# Connectors.net
KiCad netlist of a schematic drawn in Altium Designer
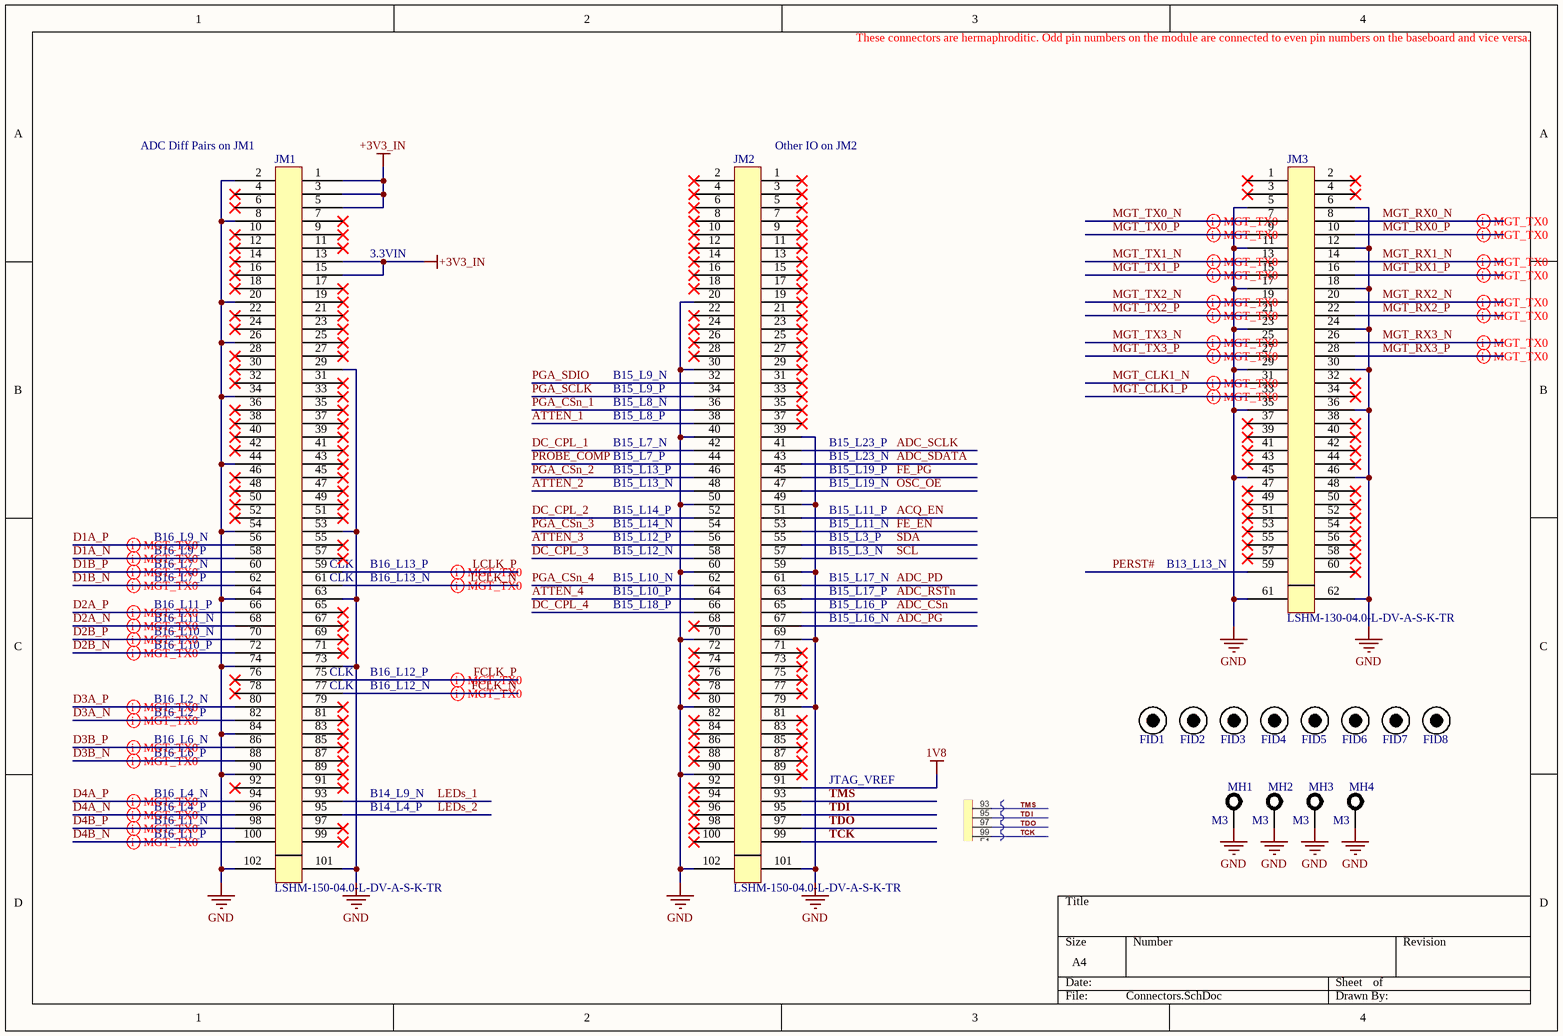
[diagram p0: Connectors.SchDoc]

(export (version "E")
  (design (tool "Eeschema 10.0.6"))
  (components
    (comp (ref "FID1") (value "PCB") (footprint "GEN_FID") (libsource (lib "DSO") (part "FID 1mm")))
    (comp (ref "FID2") (value "PCB") (footprint "GEN_FID") (libsource (lib "DSO") (part "FID 1mm")))
    (comp (ref "FID3") (value "PCB") (footprint "GEN_FID") (libsource (lib "DSO") (part "FID 1mm")))
    (comp (ref "FID4") (value "PCB") (footprint "GEN_FID") (libsource (lib "DSO") (part "FID 1mm")))
    (comp (ref "FID5") (value "PCB") (footprint "GEN_FID") (libsource (lib "DSO") (part "FID 1mm")))
    (comp (ref "FID6") (value "PCB") (footprint "GEN_FID") (libsource (lib "DSO") (part "FID 1mm")))
    (comp (ref "FID7") (value "PCB") (footprint "GEN_FID") (libsource (lib "DSO") (part "FID 1mm")))
    (comp (ref "FID8") (value "PCB") (footprint "GEN_FID") (libsource (lib "DSO") (part "FID 1mm")))
    (comp (ref "JM1")
      (value "LSHM-150-04.0-L-DV-A-S-K-TR")
      (footprint "SAM_LSHM-150-XX.X-XX-DV-A-S")
      (libsource (lib "DSO") (part "CONN LSHM-150-04.0-L-DV-A-S-K-TR"))
    )
    (comp (ref "JM2")
      (value "LSHM-150-04.0-L-DV-A-S-K-TR")
      (footprint "SAM_LSHM-150-XX.X-XX-DV-A-S")
      (libsource (lib "DSO") (part "CONN LSHM-150-04.0-L-DV-A-S-K-TR"))
    )
    (comp (ref "JM3")
      (value "LSHM-130-04.0-L-DV-A-S-K-TR")
      (footprint "SAM_LSHM-130-XX.X-XX-DV-A-S")
      (libsource (lib "DSO") (part "CONN LSHM-130-04.0-L-DV-A-S-K-TR"))
    )
    (comp (ref "MH1") (value "M3") (footprint "MH M3") (libsource (lib "DSO") (part "MH M3")))
    (comp (ref "MH2") (value "M3") (footprint "MH M3") (libsource (lib "DSO") (part "MH M3")))
    (comp (ref "MH3") (value "M3") (footprint "MH M3") (libsource (lib "DSO") (part "MH M3")))
    (comp (ref "MH4") (value "M3") (footprint "MH M3") (libsource (lib "DSO") (part "MH M3")))
  )
  (nets
    (net (code "1") (name "+3V3_IN") (class "Default")
      (node (ref "JM1") (pin "1") (pinfunction "1_1") (pintype "passive"))
      (node (ref "JM1") (pin "13") (pinfunction "13_13") (pintype "passive"))
      (node (ref "JM1") (pin "15") (pinfunction "15_15") (pintype "passive"))
      (node (ref "JM1") (pin "3") (pinfunction "3_3") (pintype "passive"))
      (node (ref "JM1") (pin "5") (pinfunction "5_5") (pintype "passive"))
    )
    (net (code "2") (name "/ACQ_EN") (class "Default")
      (node (ref "JM2") (pin "51") (pinfunction "51_51") (pintype "passive"))
    )
    (net (code "3") (name "/ADC_CSn") (class "Default")
      (node (ref "JM2") (pin "65") (pinfunction "65_65") (pintype "passive"))
    )
    (net (code "4") (name "/ADC_PD") (class "Default")
      (node (ref "JM2") (pin "61") (pinfunction "61_61") (pintype "passive"))
    )
    (net (code "5") (name "/ADC_PG") (class "Default")
      (node (ref "JM2") (pin "67") (pinfunction "67_67") (pintype "passive"))
    )
    (net (code "6") (name "/ADC_RSTn") (class "Default")
      (node (ref "JM2") (pin "63") (pinfunction "63_63") (pintype "passive"))
    )
    (net (code "7") (name "/ADC_SCLK") (class "Default")
      (node (ref "JM2") (pin "41") (pinfunction "41_41") (pintype "passive"))
    )
    (net (code "8") (name "/ADC_SDATA") (class "Default")
      (node (ref "JM2") (pin "43") (pinfunction "43_43") (pintype "passive"))
    )
    (net (code "9") (name "/ATTEN_1") (class "Default")
      (node (ref "JM2") (pin "38") (pinfunction "38_38") (pintype "passive"))
    )
    (net (code "10") (name "/ATTEN_2") (class "Default")
      (node (ref "JM2") (pin "48") (pinfunction "48_48") (pintype "passive"))
    )
    (net (code "11") (name "/ATTEN_3") (class "Default")
      (node (ref "JM2") (pin "56") (pinfunction "56_56") (pintype "passive"))
    )
    (net (code "12") (name "/ATTEN_4") (class "Default")
      (node (ref "JM2") (pin "64") (pinfunction "64_64") (pintype "passive"))
    )
    (net (code "13") (name "/D1A_N") (class "Default")
      (node (ref "JM1") (pin "58") (pinfunction "58_58") (pintype "passive"))
    )
    (net (code "14") (name "/D1A_P") (class "Default")
      (node (ref "JM1") (pin "56") (pinfunction "56_56") (pintype "passive"))
    )
    (net (code "15") (name "/D1B_N") (class "Default")
      (node (ref "JM1") (pin "62") (pinfunction "62_62") (pintype "passive"))
    )
    (net (code "16") (name "/D1B_P") (class "Default")
      (node (ref "JM1") (pin "60") (pinfunction "60_60") (pintype "passive"))
    )
    (net (code "17") (name "/D2A_N") (class "Default")
      (node (ref "JM1") (pin "68") (pinfunction "68_68") (pintype "passive"))
    )
    (net (code "18") (name "/D2A_P") (class "Default")
      (node (ref "JM1") (pin "66") (pinfunction "66_66") (pintype "passive"))
    )
    (net (code "19") (name "/D2B_N") (class "Default")
      (node (ref "JM1") (pin "72") (pinfunction "72_72") (pintype "passive"))
    )
    (net (code "20") (name "/D2B_P") (class "Default")
      (node (ref "JM1") (pin "70") (pinfunction "70_70") (pintype "passive"))
    )
    (net (code "21") (name "/D3A_N") (class "Default")
      (node (ref "JM1") (pin "82") (pinfunction "82_82") (pintype "passive"))
    )
    (net (code "22") (name "/D3A_P") (class "Default")
      (node (ref "JM1") (pin "80") (pinfunction "80_80") (pintype "passive"))
    )
    (net (code "23") (name "/D3B_N") (class "Default")
      (node (ref "JM1") (pin "88") (pinfunction "88_88") (pintype "passive"))
    )
    (net (code "24") (name "/D3B_P") (class "Default")
      (node (ref "JM1") (pin "86") (pinfunction "86_86") (pintype "passive"))
    )
    (net (code "25") (name "/D4A_N") (class "Default")
      (node (ref "JM1") (pin "96") (pinfunction "96_96") (pintype "passive"))
    )
    (net (code "26") (name "/D4A_P") (class "Default")
      (node (ref "JM1") (pin "94") (pinfunction "94_94") (pintype "passive"))
    )
    (net (code "27") (name "/D4B_N") (class "Default")
      (node (ref "JM1") (pin "100") (pinfunction "100_100") (pintype "passive"))
    )
    (net (code "28") (name "/D4B_P") (class "Default")
      (node (ref "JM1") (pin "98") (pinfunction "98_98") (pintype "passive"))
    )
    (net (code "29") (name "/DC_CPL_1") (class "Default")
      (node (ref "JM2") (pin "42") (pinfunction "42_42") (pintype "passive"))
    )
    (net (code "30") (name "/DC_CPL_2") (class "Default")
      (node (ref "JM2") (pin "52") (pinfunction "52_52") (pintype "passive"))
    )
    (net (code "31") (name "/DC_CPL_3") (class "Default")
      (node (ref "JM2") (pin "58") (pinfunction "58_58") (pintype "passive"))
    )
    (net (code "32") (name "/DC_CPL_4") (class "Default")
      (node (ref "JM2") (pin "66") (pinfunction "66_66") (pintype "passive"))
    )
    (net (code "33") (name "/FCLK_N") (class "Default")
      (node (ref "JM1") (pin "77") (pinfunction "77_77") (pintype "passive"))
    )
    (net (code "34") (name "/FCLK_P") (class "Default")
      (node (ref "JM1") (pin "75") (pinfunction "75_75") (pintype "passive"))
    )
    (net (code "35") (name "/FE_EN") (class "Default")
      (node (ref "JM2") (pin "53") (pinfunction "53_53") (pintype "passive"))
    )
    (net (code "36") (name "/FE_PG") (class "Default")
      (node (ref "JM2") (pin "45") (pinfunction "45_45") (pintype "passive"))
    )
    (net (code "37") (name "/LCLK_N") (class "Default")
      (node (ref "JM1") (pin "61") (pinfunction "61_61") (pintype "passive"))
    )
    (net (code "38") (name "/LCLK_P") (class "Default")
      (node (ref "JM1") (pin "59") (pinfunction "59_59") (pintype "passive"))
    )
    (net (code "39") (name "/LEDs_1") (class "Default")
      (node (ref "JM1") (pin "93") (pinfunction "93_93") (pintype "passive"))
    )
    (net (code "40") (name "/LEDs_2") (class "Default")
      (node (ref "JM1") (pin "95") (pinfunction "95_95") (pintype "passive"))
    )
    (net (code "41") (name "/MGT_CLK1_N") (class "Default")
      (node (ref "JM3") (pin "31") (pinfunction "31_31") (pintype "passive"))
    )
    (net (code "42") (name "/MGT_CLK1_P") (class "Default")
      (node (ref "JM3") (pin "33") (pinfunction "33_33") (pintype "passive"))
    )
    (net (code "43") (name "/MGT_RX0_N") (class "Default")
      (node (ref "JM3") (pin "8") (pinfunction "8_8") (pintype "passive"))
    )
    (net (code "44") (name "/MGT_RX0_P") (class "Default")
      (node (ref "JM3") (pin "10") (pinfunction "10_10") (pintype "passive"))
    )
    (net (code "45") (name "/MGT_RX1_N") (class "Default")
      (node (ref "JM3") (pin "14") (pinfunction "14_14") (pintype "passive"))
    )
    (net (code "46") (name "/MGT_RX1_P") (class "Default")
      (node (ref "JM3") (pin "16") (pinfunction "16_16") (pintype "passive"))
    )
    (net (code "47") (name "/MGT_RX2_N") (class "Default")
      (node (ref "JM3") (pin "20") (pinfunction "20_20") (pintype "passive"))
    )
    (net (code "48") (name "/MGT_RX2_P") (class "Default")
      (node (ref "JM3") (pin "22") (pinfunction "22_22") (pintype "passive"))
    )
    (net (code "49") (name "/MGT_RX3_N") (class "Default")
      (node (ref "JM3") (pin "26") (pinfunction "26_26") (pintype "passive"))
    )
    (net (code "50") (name "/MGT_RX3_P") (class "Default")
      (node (ref "JM3") (pin "28") (pinfunction "28_28") (pintype "passive"))
    )
    (net (code "51") (name "/MGT_TX0_N") (class "Default")
      (node (ref "JM3") (pin "7") (pinfunction "7_7") (pintype "passive"))
    )
    (net (code "52") (name "/MGT_TX0_P") (class "Default")
      (node (ref "JM3") (pin "9") (pinfunction "9_9") (pintype "passive"))
    )
    (net (code "53") (name "/MGT_TX1_N") (class "Default")
      (node (ref "JM3") (pin "13") (pinfunction "13_13") (pintype "passive"))
    )
    (net (code "54") (name "/MGT_TX1_P") (class "Default")
      (node (ref "JM3") (pin "15") (pinfunction "15_15") (pintype "passive"))
    )
    (net (code "55") (name "/MGT_TX2_N") (class "Default")
      (node (ref "JM3") (pin "19") (pinfunction "19_19") (pintype "passive"))
    )
    (net (code "56") (name "/MGT_TX2_P") (class "Default")
      (node (ref "JM3") (pin "21") (pinfunction "21_21") (pintype "passive"))
    )
    (net (code "57") (name "/MGT_TX3_N") (class "Default")
      (node (ref "JM3") (pin "25") (pinfunction "25_25") (pintype "passive"))
    )
    (net (code "58") (name "/MGT_TX3_P") (class "Default")
      (node (ref "JM3") (pin "27") (pinfunction "27_27") (pintype "passive"))
    )
    (net (code "59") (name "/OSC_OE") (class "Default")
      (node (ref "JM2") (pin "47") (pinfunction "47_47") (pintype "passive"))
    )
    (net (code "60") (name "/PERST#") (class "Default")
      (node (ref "JM3") (pin "59") (pinfunction "59_59") (pintype "passive"))
    )
    (net (code "61") (name "/PGA_CSn_1") (class "Default")
      (node (ref "JM2") (pin "36") (pinfunction "36_36") (pintype "passive"))
    )
    (net (code "62") (name "/PGA_CSn_2") (class "Default")
      (node (ref "JM2") (pin "46") (pinfunction "46_46") (pintype "passive"))
    )
    (net (code "63") (name "/PGA_CSn_3") (class "Default")
      (node (ref "JM2") (pin "54") (pinfunction "54_54") (pintype "passive"))
    )
    (net (code "64") (name "/PGA_CSn_4") (class "Default")
      (node (ref "JM2") (pin "62") (pinfunction "62_62") (pintype "passive"))
    )
    (net (code "65") (name "/PGA_SCLK") (class "Default")
      (node (ref "JM2") (pin "34") (pinfunction "34_34") (pintype "passive"))
    )
    (net (code "66") (name "/PGA_SDIO") (class "Default")
      (node (ref "JM2") (pin "32") (pinfunction "32_32") (pintype "passive"))
    )
    (net (code "67") (name "/PROBE_COMP") (class "Default")
      (node (ref "JM2") (pin "44") (pinfunction "44_44") (pintype "passive"))
    )
    (net (code "68") (name "/SCL") (class "Default")
      (node (ref "JM2") (pin "57") (pinfunction "57_57") (pintype "passive"))
    )
    (net (code "69") (name "/SDA") (class "Default")
      (node (ref "JM2") (pin "55") (pinfunction "55_55") (pintype "passive"))
    )
    (net (code "70") (name "/TCK") (class "Default")
      (node (ref "JM2") (pin "99") (pinfunction "99_99") (pintype "passive"))
    )
    (net (code "71") (name "/TDI") (class "Default")
      (node (ref "JM2") (pin "95") (pinfunction "95_95") (pintype "passive"))
    )
    (net (code "72") (name "/TDO") (class "Default")
      (node (ref "JM2") (pin "97") (pinfunction "97_97") (pintype "passive"))
    )
    (net (code "73") (name "/TMS") (class "Default")
      (node (ref "JM2") (pin "93") (pinfunction "93_93") (pintype "passive"))
    )
    (net (code "74") (name "1V8") (class "Default")
      (node (ref "JM2") (pin "91") (pinfunction "91_91") (pintype "passive"))
    )
    (net (code "75") (name "GND") (class "Default")
      (node (ref "JM1") (pin "101") (pinfunction "101_101") (pintype "passive"))
      (node (ref "JM1") (pin "102") (pinfunction "102_102") (pintype "passive"))
      (node (ref "JM1") (pin "2") (pinfunction "2_2") (pintype "passive"))
      (node (ref "JM1") (pin "20") (pinfunction "20_20") (pintype "passive"))
      (node (ref "JM1") (pin "26") (pinfunction "26_26") (pintype "passive"))
      (node (ref "JM1") (pin "29") (pinfunction "29_29") (pintype "passive"))
      (node (ref "JM1") (pin "34") (pinfunction "34_34") (pintype "passive"))
      (node (ref "JM1") (pin "44") (pinfunction "44_44") (pintype "passive"))
      (node (ref "JM1") (pin "53") (pinfunction "53_53") (pintype "passive"))
      (node (ref "JM1") (pin "54") (pinfunction "54_54") (pintype "passive"))
      (node (ref "JM1") (pin "63") (pinfunction "63_63") (pintype "passive"))
      (node (ref "JM1") (pin "64") (pinfunction "64_64") (pintype "passive"))
      (node (ref "JM1") (pin "73") (pinfunction "73_73") (pintype "passive"))
      (node (ref "JM1") (pin "74") (pinfunction "74_74") (pintype "passive"))
      (node (ref "JM1") (pin "8") (pinfunction "8_8") (pintype "passive"))
      (node (ref "JM1") (pin "84") (pinfunction "84_84") (pintype "passive"))
      (node (ref "JM1") (pin "90") (pinfunction "90_90") (pintype "passive"))
      (node (ref "JM2") (pin "101") (pinfunction "101_101") (pintype "passive"))
      (node (ref "JM2") (pin "102") (pinfunction "102_102") (pintype "passive"))
      (node (ref "JM2") (pin "20") (pinfunction "20_20") (pintype "passive"))
      (node (ref "JM2") (pin "30") (pinfunction "30_30") (pintype "passive"))
      (node (ref "JM2") (pin "39") (pinfunction "39_39") (pintype "passive"))
      (node (ref "JM2") (pin "40") (pinfunction "40_40") (pintype "passive"))
      (node (ref "JM2") (pin "49") (pinfunction "49_49") (pintype "passive"))
      (node (ref "JM2") (pin "50") (pinfunction "50_50") (pintype "passive"))
      (node (ref "JM2") (pin "59") (pinfunction "59_59") (pintype "passive"))
      (node (ref "JM2") (pin "60") (pinfunction "60_60") (pintype "passive"))
      (node (ref "JM2") (pin "69") (pinfunction "69_69") (pintype "passive"))
      (node (ref "JM2") (pin "70") (pinfunction "70_70") (pintype "passive"))
      (node (ref "JM2") (pin "79") (pinfunction "79_79") (pintype "passive"))
      (node (ref "JM2") (pin "80") (pinfunction "80_80") (pintype "passive"))
      (node (ref "JM2") (pin "90") (pinfunction "90_90") (pintype "passive"))
      (node (ref "JM3") (pin "11") (pinfunction "11_11") (pintype "passive"))
      (node (ref "JM3") (pin "12") (pinfunction "12_12") (pintype "passive"))
      (node (ref "JM3") (pin "17") (pinfunction "17_17") (pintype "passive"))
      (node (ref "JM3") (pin "18") (pinfunction "18_18") (pintype "passive"))
      (node (ref "JM3") (pin "23") (pinfunction "23_23") (pintype "passive"))
      (node (ref "JM3") (pin "24") (pinfunction "24_24") (pintype "passive"))
      (node (ref "JM3") (pin "29") (pinfunction "29_29") (pintype "passive"))
      (node (ref "JM3") (pin "30") (pinfunction "30_30") (pintype "passive"))
      (node (ref "JM3") (pin "35") (pinfunction "35_35") (pintype "passive"))
      (node (ref "JM3") (pin "36") (pinfunction "36_36") (pintype "passive"))
      (node (ref "JM3") (pin "45") (pinfunction "45_45") (pintype "passive"))
      (node (ref "JM3") (pin "46") (pinfunction "46_46") (pintype "passive"))
      (node (ref "JM3") (pin "5") (pinfunction "5_5") (pintype "passive"))
      (node (ref "JM3") (pin "6") (pinfunction "6_6") (pintype "passive"))
      (node (ref "JM3") (pin "61") (pinfunction "61_61") (pintype "passive"))
      (node (ref "JM3") (pin "62") (pinfunction "62_62") (pintype "passive"))
      (node (ref "MH1") (pin "1") (pinfunction "1_1") (pintype "passive"))
      (node (ref "MH2") (pin "1") (pinfunction "1_1") (pintype "passive"))
      (node (ref "MH3") (pin "1") (pinfunction "1_1") (pintype "passive"))
      (node (ref "MH4") (pin "1") (pinfunction "1_1") (pintype "passive"))
    )
    (net (code "76") (name "unconnected-(JM1-Pad4)") (class "Default")
      (node (ref "JM1") (pin "4") (pinfunction "4_4") (pintype "passive+no_connect"))
    )
    (net (code "77") (name "unconnected-(JM1-Pad6)") (class "Default")
      (node (ref "JM1") (pin "6") (pinfunction "6_6") (pintype "passive+no_connect"))
    )
    (net (code "78") (name "unconnected-(JM1-Pad7)") (class "Default")
      (node (ref "JM1") (pin "7") (pinfunction "7_7") (pintype "passive+no_connect"))
    )
    (net (code "79") (name "unconnected-(JM1-Pad9)") (class "Default")
      (node (ref "JM1") (pin "9") (pinfunction "9_9") (pintype "passive+no_connect"))
    )
    (net (code "80") (name "unconnected-(JM1-Pad10)") (class "Default")
      (node (ref "JM1") (pin "10") (pinfunction "10_10") (pintype "passive+no_connect"))
    )
    (net (code "81") (name "unconnected-(JM1-Pad11)") (class "Default")
      (node (ref "JM1") (pin "11") (pinfunction "11_11") (pintype "passive+no_connect"))
    )
    (net (code "82") (name "unconnected-(JM1-Pad12)") (class "Default")
      (node (ref "JM1") (pin "12") (pinfunction "12_12") (pintype "passive+no_connect"))
    )
    (net (code "83") (name "unconnected-(JM1-Pad14)") (class "Default")
      (node (ref "JM1") (pin "14") (pinfunction "14_14") (pintype "passive+no_connect"))
    )
    (net (code "84") (name "unconnected-(JM1-Pad16)") (class "Default")
      (node (ref "JM1") (pin "16") (pinfunction "16_16") (pintype "passive+no_connect"))
    )
    (net (code "85") (name "unconnected-(JM1-Pad17)") (class "Default")
      (node (ref "JM1") (pin "17") (pinfunction "17_17") (pintype "passive+no_connect"))
    )
    (net (code "86") (name "unconnected-(JM1-Pad18)") (class "Default")
      (node (ref "JM1") (pin "18") (pinfunction "18_18") (pintype "passive+no_connect"))
    )
    (net (code "87") (name "unconnected-(JM1-Pad19)") (class "Default")
      (node (ref "JM1") (pin "19") (pinfunction "19_19") (pintype "passive+no_connect"))
    )
    (net (code "88") (name "unconnected-(JM1-Pad21)") (class "Default")
      (node (ref "JM1") (pin "21") (pinfunction "21_21") (pintype "passive+no_connect"))
    )
    (net (code "89") (name "unconnected-(JM1-Pad22)") (class "Default")
      (node (ref "JM1") (pin "22") (pinfunction "22_22") (pintype "passive+no_connect"))
    )
    (net (code "90") (name "unconnected-(JM1-Pad23)") (class "Default")
      (node (ref "JM1") (pin "23") (pinfunction "23_23") (pintype "passive+no_connect"))
    )
    (net (code "91") (name "unconnected-(JM1-Pad24)") (class "Default")
      (node (ref "JM1") (pin "24") (pinfunction "24_24") (pintype "passive+no_connect"))
    )
    (net (code "92") (name "unconnected-(JM1-Pad25)") (class "Default")
      (node (ref "JM1") (pin "25") (pinfunction "25_25") (pintype "passive+no_connect"))
    )
    (net (code "93") (name "unconnected-(JM1-Pad27)") (class "Default")
      (node (ref "JM1") (pin "27") (pinfunction "27_27") (pintype "passive+no_connect"))
    )
    (net (code "94") (name "unconnected-(JM1-Pad28)") (class "Default")
      (node (ref "JM1") (pin "28") (pinfunction "28_28") (pintype "passive+no_connect"))
    )
    (net (code "95") (name "unconnected-(JM1-Pad30)") (class "Default")
      (node (ref "JM1") (pin "30") (pinfunction "30_30") (pintype "passive+no_connect"))
    )
    (net (code "96") (name "unconnected-(JM1-Pad31)") (class "Default")
      (node (ref "JM1") (pin "31") (pinfunction "31_31") (pintype "passive+no_connect"))
    )
    (net (code "97") (name "unconnected-(JM1-Pad32)") (class "Default")
      (node (ref "JM1") (pin "32") (pinfunction "32_32") (pintype "passive+no_connect"))
    )
    (net (code "98") (name "unconnected-(JM1-Pad33)") (class "Default")
      (node (ref "JM1") (pin "33") (pinfunction "33_33") (pintype "passive+no_connect"))
    )
    (net (code "99") (name "unconnected-(JM1-Pad35)") (class "Default")
      (node (ref "JM1") (pin "35") (pinfunction "35_35") (pintype "passive+no_connect"))
    )
    (net (code "100") (name "unconnected-(JM1-Pad36)") (class "Default")
      (node (ref "JM1") (pin "36") (pinfunction "36_36") (pintype "passive+no_connect"))
    )
    (net (code "101") (name "unconnected-(JM1-Pad37)") (class "Default")
      (node (ref "JM1") (pin "37") (pinfunction "37_37") (pintype "passive+no_connect"))
    )
    (net (code "102") (name "unconnected-(JM1-Pad38)") (class "Default")
      (node (ref "JM1") (pin "38") (pinfunction "38_38") (pintype "passive+no_connect"))
    )
    (net (code "103") (name "unconnected-(JM1-Pad39)") (class "Default")
      (node (ref "JM1") (pin "39") (pinfunction "39_39") (pintype "passive+no_connect"))
    )
    (net (code "104") (name "unconnected-(JM1-Pad40)") (class "Default")
      (node (ref "JM1") (pin "40") (pinfunction "40_40") (pintype "passive+no_connect"))
    )
    (net (code "105") (name "unconnected-(JM1-Pad41)") (class "Default")
      (node (ref "JM1") (pin "41") (pinfunction "41_41") (pintype "passive+no_connect"))
    )
    (net (code "106") (name "unconnected-(JM1-Pad42)") (class "Default")
      (node (ref "JM1") (pin "42") (pinfunction "42_42") (pintype "passive+no_connect"))
    )
    (net (code "107") (name "unconnected-(JM1-Pad43)") (class "Default")
      (node (ref "JM1") (pin "43") (pinfunction "43_43") (pintype "passive+no_connect"))
    )
    (net (code "108") (name "unconnected-(JM1-Pad45)") (class "Default")
      (node (ref "JM1") (pin "45") (pinfunction "45_45") (pintype "passive+no_connect"))
    )
    (net (code "109") (name "unconnected-(JM1-Pad46)") (class "Default")
      (node (ref "JM1") (pin "46") (pinfunction "46_46") (pintype "passive+no_connect"))
    )
    (net (code "110") (name "unconnected-(JM1-Pad47)") (class "Default")
      (node (ref "JM1") (pin "47") (pinfunction "47_47") (pintype "passive+no_connect"))
    )
    (net (code "111") (name "unconnected-(JM1-Pad48)") (class "Default")
      (node (ref "JM1") (pin "48") (pinfunction "48_48") (pintype "passive+no_connect"))
    )
    (net (code "112") (name "unconnected-(JM1-Pad49)") (class "Default")
      (node (ref "JM1") (pin "49") (pinfunction "49_49") (pintype "passive+no_connect"))
    )
    (net (code "113") (name "unconnected-(JM1-Pad50)") (class "Default")
      (node (ref "JM1") (pin "50") (pinfunction "50_50") (pintype "passive+no_connect"))
    )
    (net (code "114") (name "unconnected-(JM1-Pad51)") (class "Default")
      (node (ref "JM1") (pin "51") (pinfunction "51_51") (pintype "passive+no_connect"))
    )
    (net (code "115") (name "unconnected-(JM1-Pad52)") (class "Default")
      (node (ref "JM1") (pin "52") (pinfunction "52_52") (pintype "passive+no_connect"))
    )
    (net (code "116") (name "unconnected-(JM1-Pad55)") (class "Default")
      (node (ref "JM1") (pin "55") (pinfunction "55_55") (pintype "passive+no_connect"))
    )
    (net (code "117") (name "unconnected-(JM1-Pad57)") (class "Default")
      (node (ref "JM1") (pin "57") (pinfunction "57_57") (pintype "passive+no_connect"))
    )
    (net (code "118") (name "unconnected-(JM1-Pad65)") (class "Default")
      (node (ref "JM1") (pin "65") (pinfunction "65_65") (pintype "passive+no_connect"))
    )
    (net (code "119") (name "unconnected-(JM1-Pad67)") (class "Default")
      (node (ref "JM1") (pin "67") (pinfunction "67_67") (pintype "passive+no_connect"))
    )
    (net (code "120") (name "unconnected-(JM1-Pad69)") (class "Default")
      (node (ref "JM1") (pin "69") (pinfunction "69_69") (pintype "passive+no_connect"))
    )
    (net (code "121") (name "unconnected-(JM1-Pad71)") (class "Default")
      (node (ref "JM1") (pin "71") (pinfunction "71_71") (pintype "passive+no_connect"))
    )
    (net (code "122") (name "unconnected-(JM1-Pad76)") (class "Default")
      (node (ref "JM1") (pin "76") (pinfunction "76_76") (pintype "passive+no_connect"))
    )
    (net (code "123") (name "unconnected-(JM1-Pad78)") (class "Default")
      (node (ref "JM1") (pin "78") (pinfunction "78_78") (pintype "passive+no_connect"))
    )
    (net (code "124") (name "unconnected-(JM1-Pad79)") (class "Default")
      (node (ref "JM1") (pin "79") (pinfunction "79_79") (pintype "passive+no_connect"))
    )
    (net (code "125") (name "unconnected-(JM1-Pad81)") (class "Default")
      (node (ref "JM1") (pin "81") (pinfunction "81_81") (pintype "passive+no_connect"))
    )
    (net (code "126") (name "unconnected-(JM1-Pad83)") (class "Default")
      (node (ref "JM1") (pin "83") (pinfunction "83_83") (pintype "passive+no_connect"))
    )
    (net (code "127") (name "unconnected-(JM1-Pad85)") (class "Default")
      (node (ref "JM1") (pin "85") (pinfunction "85_85") (pintype "passive+no_connect"))
    )
    (net (code "128") (name "unconnected-(JM1-Pad87)") (class "Default")
      (node (ref "JM1") (pin "87") (pinfunction "87_87") (pintype "passive+no_connect"))
    )
    (net (code "129") (name "unconnected-(JM1-Pad89)") (class "Default")
      (node (ref "JM1") (pin "89") (pinfunction "89_89") (pintype "passive+no_connect"))
    )
    (net (code "130") (name "unconnected-(JM1-Pad91)") (class "Default")
      (node (ref "JM1") (pin "91") (pinfunction "91_91") (pintype "passive+no_connect"))
    )
    (net (code "131") (name "unconnected-(JM1-Pad92)") (class "Default")
      (node (ref "JM1") (pin "92") (pinfunction "92_92") (pintype "passive+no_connect"))
    )
    (net (code "132") (name "unconnected-(JM1-Pad97)") (class "Default")
      (node (ref "JM1") (pin "97") (pinfunction "97_97") (pintype "passive+no_connect"))
    )
    (net (code "133") (name "unconnected-(JM1-Pad99)") (class "Default")
      (node (ref "JM1") (pin "99") (pinfunction "99_99") (pintype "passive+no_connect"))
    )
    (net (code "134") (name "unconnected-(JM2-Pad1)") (class "Default")
      (node (ref "JM2") (pin "1") (pinfunction "1_1") (pintype "passive+no_connect"))
    )
    (net (code "135") (name "unconnected-(JM2-Pad2)") (class "Default")
      (node (ref "JM2") (pin "2") (pinfunction "2_2") (pintype "passive+no_connect"))
    )
    (net (code "136") (name "unconnected-(JM2-Pad3)") (class "Default")
      (node (ref "JM2") (pin "3") (pinfunction "3_3") (pintype "passive+no_connect"))
    )
    (net (code "137") (name "unconnected-(JM2-Pad4)") (class "Default")
      (node (ref "JM2") (pin "4") (pinfunction "4_4") (pintype "passive+no_connect"))
    )
    (net (code "138") (name "unconnected-(JM2-Pad5)") (class "Default")
      (node (ref "JM2") (pin "5") (pinfunction "5_5") (pintype "passive+no_connect"))
    )
    (net (code "139") (name "unconnected-(JM2-Pad6)") (class "Default")
      (node (ref "JM2") (pin "6") (pinfunction "6_6") (pintype "passive+no_connect"))
    )
    (net (code "140") (name "unconnected-(JM2-Pad7)") (class "Default")
      (node (ref "JM2") (pin "7") (pinfunction "7_7") (pintype "passive+no_connect"))
    )
    (net (code "141") (name "unconnected-(JM2-Pad8)") (class "Default")
      (node (ref "JM2") (pin "8") (pinfunction "8_8") (pintype "passive+no_connect"))
    )
    (net (code "142") (name "unconnected-(JM2-Pad9)") (class "Default")
      (node (ref "JM2") (pin "9") (pinfunction "9_9") (pintype "passive+no_connect"))
    )
    (net (code "143") (name "unconnected-(JM2-Pad10)") (class "Default")
      (node (ref "JM2") (pin "10") (pinfunction "10_10") (pintype "passive+no_connect"))
    )
    (net (code "144") (name "unconnected-(JM2-Pad11)") (class "Default")
      (node (ref "JM2") (pin "11") (pinfunction "11_11") (pintype "passive+no_connect"))
    )
    (net (code "145") (name "unconnected-(JM2-Pad12)") (class "Default")
      (node (ref "JM2") (pin "12") (pinfunction "12_12") (pintype "passive+no_connect"))
    )
    (net (code "146") (name "unconnected-(JM2-Pad13)") (class "Default")
      (node (ref "JM2") (pin "13") (pinfunction "13_13") (pintype "passive+no_connect"))
    )
    (net (code "147") (name "unconnected-(JM2-Pad14)") (class "Default")
      (node (ref "JM2") (pin "14") (pinfunction "14_14") (pintype "passive+no_connect"))
    )
    (net (code "148") (name "unconnected-(JM2-Pad15)") (class "Default")
      (node (ref "JM2") (pin "15") (pinfunction "15_15") (pintype "passive+no_connect"))
    )
    (net (code "149") (name "unconnected-(JM2-Pad16)") (class "Default")
      (node (ref "JM2") (pin "16") (pinfunction "16_16") (pintype "passive+no_connect"))
    )
    (net (code "150") (name "unconnected-(JM2-Pad17)") (class "Default")
      (node (ref "JM2") (pin "17") (pinfunction "17_17") (pintype "passive+no_connect"))
    )
    (net (code "151") (name "unconnected-(JM2-Pad18)") (class "Default")
      (node (ref "JM2") (pin "18") (pinfunction "18_18") (pintype "passive+no_connect"))
    )
    (net (code "152") (name "unconnected-(JM2-Pad19)") (class "Default")
      (node (ref "JM2") (pin "19") (pinfunction "19_19") (pintype "passive+no_connect"))
    )
    (net (code "153") (name "unconnected-(JM2-Pad21)") (class "Default")
      (node (ref "JM2") (pin "21") (pinfunction "21_21") (pintype "passive+no_connect"))
    )
    (net (code "154") (name "unconnected-(JM2-Pad22)") (class "Default")
      (node (ref "JM2") (pin "22") (pinfunction "22_22") (pintype "passive+no_connect"))
    )
    (net (code "155") (name "unconnected-(JM2-Pad23)") (class "Default")
      (node (ref "JM2") (pin "23") (pinfunction "23_23") (pintype "passive+no_connect"))
    )
    (net (code "156") (name "unconnected-(JM2-Pad24)") (class "Default")
      (node (ref "JM2") (pin "24") (pinfunction "24_24") (pintype "passive+no_connect"))
    )
    (net (code "157") (name "unconnected-(JM2-Pad25)") (class "Default")
      (node (ref "JM2") (pin "25") (pinfunction "25_25") (pintype "passive+no_connect"))
    )
    (net (code "158") (name "unconnected-(JM2-Pad26)") (class "Default")
      (node (ref "JM2") (pin "26") (pinfunction "26_26") (pintype "passive+no_connect"))
    )
    (net (code "159") (name "unconnected-(JM2-Pad27)") (class "Default")
      (node (ref "JM2") (pin "27") (pinfunction "27_27") (pintype "passive+no_connect"))
    )
    (net (code "160") (name "unconnected-(JM2-Pad28)") (class "Default")
      (node (ref "JM2") (pin "28") (pinfunction "28_28") (pintype "passive+no_connect"))
    )
    (net (code "161") (name "unconnected-(JM2-Pad29)") (class "Default")
      (node (ref "JM2") (pin "29") (pinfunction "29_29") (pintype "passive+no_connect"))
    )
    (net (code "162") (name "unconnected-(JM2-Pad31)") (class "Default")
      (node (ref "JM2") (pin "31") (pinfunction "31_31") (pintype "passive+no_connect"))
    )
    (net (code "163") (name "unconnected-(JM2-Pad33)") (class "Default")
      (node (ref "JM2") (pin "33") (pinfunction "33_33") (pintype "passive+no_connect"))
    )
    (net (code "164") (name "unconnected-(JM2-Pad35)") (class "Default")
      (node (ref "JM2") (pin "35") (pinfunction "35_35") (pintype "passive+no_connect"))
    )
    (net (code "165") (name "unconnected-(JM2-Pad37)") (class "Default")
      (node (ref "JM2") (pin "37") (pinfunction "37_37") (pintype "passive+no_connect"))
    )
    (net (code "166") (name "unconnected-(JM2-Pad68)") (class "Default")
      (node (ref "JM2") (pin "68") (pinfunction "68_68") (pintype "passive+no_connect"))
    )
    (net (code "167") (name "unconnected-(JM2-Pad71)") (class "Default")
      (node (ref "JM2") (pin "71") (pinfunction "71_71") (pintype "passive+no_connect"))
    )
    (net (code "168") (name "unconnected-(JM2-Pad72)") (class "Default")
      (node (ref "JM2") (pin "72") (pinfunction "72_72") (pintype "passive+no_connect"))
    )
    (net (code "169") (name "unconnected-(JM2-Pad73)") (class "Default")
      (node (ref "JM2") (pin "73") (pinfunction "73_73") (pintype "passive+no_connect"))
    )
    (net (code "170") (name "unconnected-(JM2-Pad74)") (class "Default")
      (node (ref "JM2") (pin "74") (pinfunction "74_74") (pintype "passive+no_connect"))
    )
    (net (code "171") (name "unconnected-(JM2-Pad75)") (class "Default")
      (node (ref "JM2") (pin "75") (pinfunction "75_75") (pintype "passive+no_connect"))
    )
    (net (code "172") (name "unconnected-(JM2-Pad76)") (class "Default")
      (node (ref "JM2") (pin "76") (pinfunction "76_76") (pintype "passive+no_connect"))
    )
    (net (code "173") (name "unconnected-(JM2-Pad77)") (class "Default")
      (node (ref "JM2") (pin "77") (pinfunction "77_77") (pintype "passive+no_connect"))
    )
    (net (code "174") (name "unconnected-(JM2-Pad78)") (class "Default")
      (node (ref "JM2") (pin "78") (pinfunction "78_78") (pintype "passive+no_connect"))
    )
    (net (code "175") (name "unconnected-(JM2-Pad81)") (class "Default")
      (node (ref "JM2") (pin "81") (pinfunction "81_81") (pintype "passive+no_connect"))
    )
    (net (code "176") (name "unconnected-(JM2-Pad82)") (class "Default")
      (node (ref "JM2") (pin "82") (pinfunction "82_82") (pintype "passive+no_connect"))
    )
    (net (code "177") (name "unconnected-(JM2-Pad83)") (class "Default")
      (node (ref "JM2") (pin "83") (pinfunction "83_83") (pintype "passive+no_connect"))
    )
    (net (code "178") (name "unconnected-(JM2-Pad84)") (class "Default")
      (node (ref "JM2") (pin "84") (pinfunction "84_84") (pintype "passive+no_connect"))
    )
    (net (code "179") (name "unconnected-(JM2-Pad85)") (class "Default")
      (node (ref "JM2") (pin "85") (pinfunction "85_85") (pintype "passive+no_connect"))
    )
    (net (code "180") (name "unconnected-(JM2-Pad86)") (class "Default")
      (node (ref "JM2") (pin "86") (pinfunction "86_86") (pintype "passive+no_connect"))
    )
    (net (code "181") (name "unconnected-(JM2-Pad87)") (class "Default")
      (node (ref "JM2") (pin "87") (pinfunction "87_87") (pintype "passive+no_connect"))
    )
    (net (code "182") (name "unconnected-(JM2-Pad88)") (class "Default")
      (node (ref "JM2") (pin "88") (pinfunction "88_88") (pintype "passive+no_connect"))
    )
    (net (code "183") (name "unconnected-(JM2-Pad89)") (class "Default")
      (node (ref "JM2") (pin "89") (pinfunction "89_89") (pintype "passive+no_connect"))
    )
    (net (code "184") (name "unconnected-(JM2-Pad92)") (class "Default")
      (node (ref "JM2") (pin "92") (pinfunction "92_92") (pintype "passive+no_connect"))
    )
    (net (code "185") (name "unconnected-(JM2-Pad94)") (class "Default")
      (node (ref "JM2") (pin "94") (pinfunction "94_94") (pintype "passive+no_connect"))
    )
    (net (code "186") (name "unconnected-(JM2-Pad96)") (class "Default")
      (node (ref "JM2") (pin "96") (pinfunction "96_96") (pintype "passive+no_connect"))
    )
    (net (code "187") (name "unconnected-(JM2-Pad98)") (class "Default")
      (node (ref "JM2") (pin "98") (pinfunction "98_98") (pintype "passive+no_connect"))
    )
    (net (code "188") (name "unconnected-(JM2-Pad100)") (class "Default")
      (node (ref "JM2") (pin "100") (pinfunction "100_100") (pintype "passive+no_connect"))
    )
    (net (code "189") (name "unconnected-(JM3-Pad1)") (class "Default")
      (node (ref "JM3") (pin "1") (pinfunction "1_1") (pintype "passive+no_connect"))
    )
    (net (code "190") (name "unconnected-(JM3-Pad2)") (class "Default")
      (node (ref "JM3") (pin "2") (pinfunction "2_2") (pintype "passive+no_connect"))
    )
    (net (code "191") (name "unconnected-(JM3-Pad3)") (class "Default")
      (node (ref "JM3") (pin "3") (pinfunction "3_3") (pintype "passive+no_connect"))
    )
    (net (code "192") (name "unconnected-(JM3-Pad4)") (class "Default")
      (node (ref "JM3") (pin "4") (pinfunction "4_4") (pintype "passive+no_connect"))
    )
    (net (code "193") (name "unconnected-(JM3-Pad32)") (class "Default")
      (node (ref "JM3") (pin "32") (pinfunction "32_32") (pintype "passive+no_connect"))
    )
    (net (code "194") (name "unconnected-(JM3-Pad34)") (class "Default")
      (node (ref "JM3") (pin "34") (pinfunction "34_34") (pintype "passive+no_connect"))
    )
    (net (code "195") (name "unconnected-(JM3-Pad37)") (class "Default")
      (node (ref "JM3") (pin "37") (pinfunction "37_37") (pintype "passive+no_connect"))
    )
    (net (code "196") (name "unconnected-(JM3-Pad38)") (class "Default")
      (node (ref "JM3") (pin "38") (pinfunction "38_38") (pintype "passive+no_connect"))
    )
    (net (code "197") (name "unconnected-(JM3-Pad39)") (class "Default")
      (node (ref "JM3") (pin "39") (pinfunction "39_39") (pintype "passive+no_connect"))
    )
    (net (code "198") (name "unconnected-(JM3-Pad40)") (class "Default")
      (node (ref "JM3") (pin "40") (pinfunction "40_40") (pintype "passive+no_connect"))
    )
    (net (code "199") (name "unconnected-(JM3-Pad41)") (class "Default")
      (node (ref "JM3") (pin "41") (pinfunction "41_41") (pintype "passive+no_connect"))
    )
    (net (code "200") (name "unconnected-(JM3-Pad42)") (class "Default")
      (node (ref "JM3") (pin "42") (pinfunction "42_42") (pintype "passive+no_connect"))
    )
    (net (code "201") (name "unconnected-(JM3-Pad43)") (class "Default")
      (node (ref "JM3") (pin "43") (pinfunction "43_43") (pintype "passive+no_connect"))
    )
    (net (code "202") (name "unconnected-(JM3-Pad44)") (class "Default")
      (node (ref "JM3") (pin "44") (pinfunction "44_44") (pintype "passive+no_connect"))
    )
    (net (code "203") (name "unconnected-(JM3-Pad47)") (class "Default")
      (node (ref "JM3") (pin "47") (pinfunction "47_47") (pintype "passive+no_connect"))
    )
    (net (code "204") (name "unconnected-(JM3-Pad48)") (class "Default")
      (node (ref "JM3") (pin "48") (pinfunction "48_48") (pintype "passive+no_connect"))
    )
    (net (code "205") (name "unconnected-(JM3-Pad49)") (class "Default")
      (node (ref "JM3") (pin "49") (pinfunction "49_49") (pintype "passive+no_connect"))
    )
    (net (code "206") (name "unconnected-(JM3-Pad50)") (class "Default")
      (node (ref "JM3") (pin "50") (pinfunction "50_50") (pintype "passive+no_connect"))
    )
    (net (code "207") (name "unconnected-(JM3-Pad51)") (class "Default")
      (node (ref "JM3") (pin "51") (pinfunction "51_51") (pintype "passive+no_connect"))
    )
    (net (code "208") (name "unconnected-(JM3-Pad52)") (class "Default")
      (node (ref "JM3") (pin "52") (pinfunction "52_52") (pintype "passive+no_connect"))
    )
    (net (code "209") (name "unconnected-(JM3-Pad53)") (class "Default")
      (node (ref "JM3") (pin "53") (pinfunction "53_53") (pintype "passive+no_connect"))
    )
    (net (code "210") (name "unconnected-(JM3-Pad54)") (class "Default")
      (node (ref "JM3") (pin "54") (pinfunction "54_54") (pintype "passive+no_connect"))
    )
    (net (code "211") (name "unconnected-(JM3-Pad55)") (class "Default")
      (node (ref "JM3") (pin "55") (pinfunction "55_55") (pintype "passive+no_connect"))
    )
    (net (code "212") (name "unconnected-(JM3-Pad56)") (class "Default")
      (node (ref "JM3") (pin "56") (pinfunction "56_56") (pintype "passive+no_connect"))
    )
    (net (code "213") (name "unconnected-(JM3-Pad57)") (class "Default")
      (node (ref "JM3") (pin "57") (pinfunction "57_57") (pintype "passive+no_connect"))
    )
    (net (code "214") (name "unconnected-(JM3-Pad58)") (class "Default")
      (node (ref "JM3") (pin "58") (pinfunction "58_58") (pintype "passive+no_connect"))
    )
    (net (code "215") (name "unconnected-(JM3-Pad60)") (class "Default")
      (node (ref "JM3") (pin "60") (pinfunction "60_60") (pintype "passive+no_connect"))
    )
  )
)
